# Quad_FC_power_V10_0.net
KiCad netlist of a schematic drawn in Altium Designer
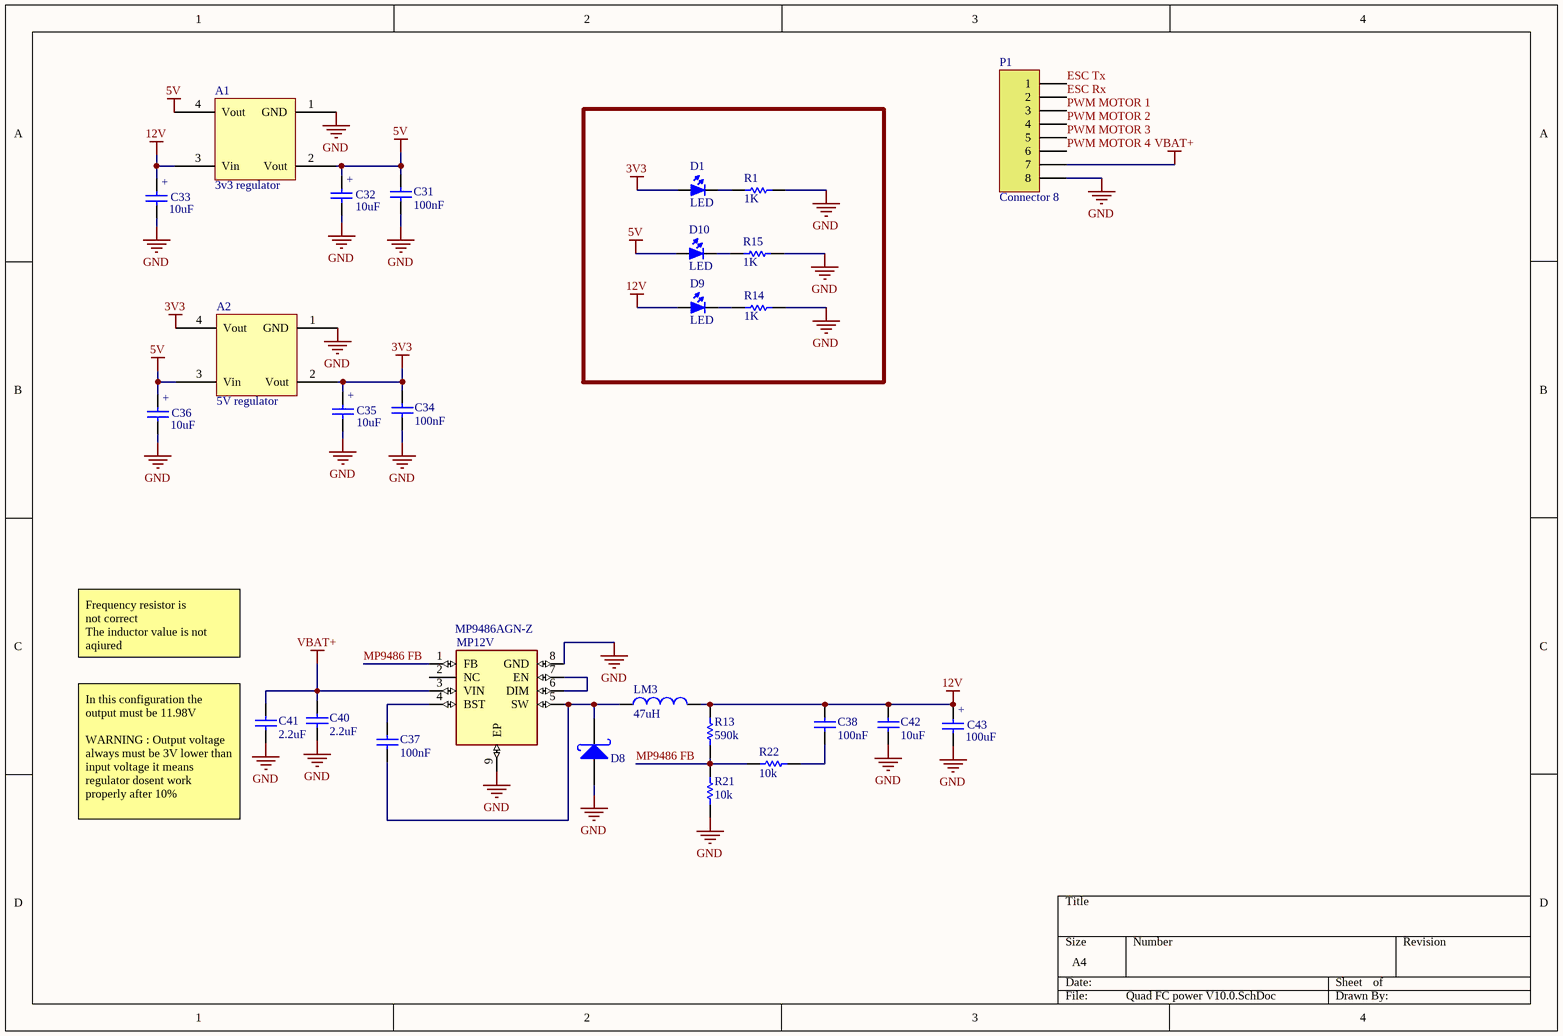
[diagram p0: Quad FC power V10.0.SchDoc]

(export (version "E")
  (design (tool "Eeschema 10.0.6"))
  (components
    (comp (ref "A1")
      (value "3v3 regulator")
      (footprint "SOT230P700X180-4N")
      (libsource (lib "Integrated_Library1") (part "ams1117"))
    )
    (comp (ref "A2")
      (value "5V regulator")
      (footprint "SOT230P700X180-4N")
      (libsource (lib "Integrated_Library1") (part "ams1117"))
    )
    (comp (ref "C31")
      (value "100nF")
      (footprint "CAP0603")
      (description "F407VET6 Power CAP")
      (fields (field (name "DESIGNER") "Abbas Basereh"))
      (libsource (lib "2017AbbasBasereh9365731239 -ver1") (part "CAP SMD PACKAGE"))
    )
    (comp (ref "C32")
      (value "10uF")
      (footprint "MY_CAP_SMD-B")
      (description "3.5X2.8MM")
      (libsource (lib "AMINLIB") (part "CAP_TANTAL_B"))
    )
    (comp (ref "C33")
      (value "10uF")
      (footprint "MY_CAP_SMD-B")
      (description "3.5X2.8MM")
      (libsource (lib "AMINLIB") (part "CAP_TANTAL_B"))
    )
    (comp (ref "C34")
      (value "100nF")
      (footprint "CAP0603")
      (description "F407VET6 Power CAP")
      (fields (field (name "DESIGNER") "Abbas Basereh"))
      (libsource (lib "2017AbbasBasereh9365731239 -ver1") (part "CAP SMD PACKAGE"))
    )
    (comp (ref "C35")
      (value "10uF")
      (footprint "MY_CAP_SMD-B")
      (description "3.5X2.8MM")
      (libsource (lib "AMINLIB") (part "CAP_TANTAL_B"))
    )
    (comp (ref "C36")
      (value "10uF")
      (footprint "MY_CAP_SMD-B")
      (description "3.5X2.8MM")
      (libsource (lib "AMINLIB") (part "CAP_TANTAL_B"))
    )
    (comp (ref "C37")
      (value "100nF")
      (footprint "CAP0603")
      (description "F407VET6 Power CAP")
      (fields (field (name "DESIGNER") "Abbas Basereh"))
      (libsource (lib "2017AbbasBasereh9365731239 -ver1") (part "CAP SMD PACKAGE"))
    )
    (comp (ref "C38")
      (value "100nF")
      (footprint "CAP0603")
      (description "F407VET6 Power CAP")
      (fields (field (name "DESIGNER") "Abbas Basereh"))
      (libsource (lib "2017AbbasBasereh9365731239 -ver1") (part "CAP SMD PACKAGE"))
    )
    (comp (ref "C40")
      (value "2.2uF")
      (footprint "CAPC3413X12N")
      (description "CAP 0805")
      (fields (field (name "DESIGNER") "Abbas Basereh"))
      (libsource (lib "2017AbbasBasereh9365731239 -ver1") (part "CAP SMD 0805"))
    )
    (comp (ref "C41")
      (value "2.2uF")
      (footprint "CAPC3413X12N")
      (description "CAP 0805")
      (fields (field (name "DESIGNER") "Abbas Basereh"))
      (libsource (lib "2017AbbasBasereh9365731239 -ver1") (part "CAP SMD 0805"))
    )
    (comp (ref "C42")
      (value "10uF")
      (footprint "CAPC3413X12N")
      (description "CAP 0805")
      (fields (field (name "DESIGNER") "Abbas Basereh"))
      (libsource (lib "2017AbbasBasereh9365731239 -ver1") (part "CAP SMD 0805"))
    )
    (comp (ref "C43")
      (value "100uF")
      (footprint "MY_CAP_SMD-B")
      (description "3.5X2.8MM")
      (libsource (lib "AMINLIB") (part "CAP_TANTAL_B"))
    )
    (comp (ref "D1")
      (value "LED")
      (footprint "0603 - LED")
      (description "Led")
      (fields (field (name "PUBLISHER") "Altium Limited"))
      (libsource (lib "Sajad_Altium_Library") (part "LED"))
    )
    (comp (ref "D8")
      (value "SS34")
      (footprint "SS34:DIOM4226X244N")
      (fields
        (field (name "MANUFACTURER") "ON Semiconductor/Fairchild")
        (field (name "DESIGNER") "Abbas Basereh")
      )
      (libsource (lib "2017AbbasBasereh9365731239 -ver1") (part "1n5822 SMD"))
    )
    (comp (ref "D9")
      (value "LED")
      (footprint "0603 - LED")
      (description "Led")
      (fields (field (name "PUBLISHER") "Altium Limited"))
      (libsource (lib "Sajad_Altium_Library") (part "LED"))
    )
    (comp (ref "D10")
      (value "LED")
      (footprint "0603 - LED")
      (description "Led")
      (fields (field (name "PUBLISHER") "Altium Limited"))
      (libsource (lib "Sajad_Altium_Library") (part "LED"))
    )
    (comp (ref "LM3")
      (value "47uH")
      (footprint "RLS-105:IND_RLS-105")
      (description "Inductor")
      (fields (field (name "PUBLISHER") "Altium Limited"))
      (libsource (lib "2017AbbasBasereh9365731239 -ver1") (part "L SMA 0.25W"))
    )
    (comp (ref "MP12V")
      (value "MP9486AGN-Z")
      (footprint "SOIC127P600X170-9N")
      (description "Buck Switching Regulator IC Positive Fixed 5V 1 Output 1A 8-SOIC (0.154, 3.90mm Width) Exposed Pad")
      (fields (field (name "MF") "Monolithic Power"))
      (libsource (lib "MP9486AGN-Z") (part "MP9486AGN-Z"))
    )
    (comp (ref "P1")
      (value "Connector 8")
      (footprint "JST B8B-PH-K")
      (description "Connector, 8-Pin2.5mm")
      (fields (field (name "PUBLISHER") "Altium Limited"))
      (libsource (lib "Sajad_Altium_Library") (part "Connector1x8"))
    )
    (comp (ref "R1")
      (value "1K")
      (footprint "RES0603")
      (description "TOTAL SMD RESISTOR PACK")
      (fields (field (name "DESIGNER") "Abbas Basereh"))
      (libsource (lib "2017AbbasBasereh9365731239 -ver1") (part "RES SMD PACKAGE"))
    )
    (comp (ref "R13")
      (value "590k")
      (footprint "RES0603")
      (description "To Limit current")
      (fields (field (name "DESIGNER") "Abbas Basereh"))
      (libsource (lib "2017AbbasBasereh9365731239 -ver1") (part "RES SMD PACKAGE"))
    )
    (comp (ref "R14")
      (value "1K")
      (footprint "RES0603")
      (description "TOTAL SMD RESISTOR PACK")
      (fields (field (name "DESIGNER") "Abbas Basereh"))
      (libsource (lib "2017AbbasBasereh9365731239 -ver1") (part "RES SMD PACKAGE"))
    )
    (comp (ref "R15")
      (value "1K")
      (footprint "RES0603")
      (description "TOTAL SMD RESISTOR PACK")
      (fields (field (name "DESIGNER") "Abbas Basereh"))
      (libsource (lib "2017AbbasBasereh9365731239 -ver1") (part "RES SMD PACKAGE"))
    )
    (comp (ref "R21")
      (value "10k")
      (footprint "RES0603")
      (description "To Limit current")
      (fields (field (name "DESIGNER") "Abbas Basereh"))
      (libsource (lib "2017AbbasBasereh9365731239 -ver1") (part "RES SMD PACKAGE"))
    )
    (comp (ref "R22")
      (value "10k")
      (footprint "RES0603")
      (description "To Limit current")
      (fields (field (name "DESIGNER") "Abbas Basereh"))
      (libsource (lib "2017AbbasBasereh9365731239 -ver1") (part "RES SMD PACKAGE"))
    )
  )
  (nets
    (net (code "1") (name "/ESC Rx") (class "Default")
      (node (ref "P1") (pin "2") (pinfunction "2_2") (pintype "passive"))
    )
    (net (code "2") (name "/ESC Tx") (class "Default")
      (node (ref "P1") (pin "1") (pinfunction "1_1") (pintype "passive"))
    )
    (net (code "3") (name "/MP9486 FB") (class "Default")
      (node (ref "MP12V") (pin "1") (pinfunction "FB_1") (pintype "bidirectional"))
      (node (ref "R13") (pin "1") (pinfunction "1_1") (pintype "passive"))
      (node (ref "R21") (pin "2") (pinfunction "2_2") (pintype "passive"))
      (node (ref "R22") (pin "2") (pinfunction "2_2") (pintype "passive"))
    )
    (net (code "4") (name "/PWM MOTOR 1") (class "Default")
      (node (ref "P1") (pin "3") (pinfunction "3_3") (pintype "passive"))
    )
    (net (code "5") (name "/PWM MOTOR 2") (class "Default")
      (node (ref "P1") (pin "4") (pinfunction "4_4") (pintype "passive"))
    )
    (net (code "6") (name "/PWM MOTOR 3") (class "Default")
      (node (ref "P1") (pin "5") (pinfunction "5_5") (pintype "passive"))
    )
    (net (code "7") (name "/PWM MOTOR 4") (class "Default")
      (node (ref "P1") (pin "6") (pinfunction "6_6") (pintype "passive"))
    )
    (net (code "8") (name "3V3") (class "Default")
      (node (ref "A2") (pin "2") (pinfunction "Vout_2") (pintype "passive"))
      (node (ref "A2") (pin "4") (pinfunction "Vout_4") (pintype "passive"))
      (node (ref "C34") (pin "2") (pinfunction "2_2") (pintype "passive"))
      (node (ref "C35") (pin "+") (pinfunction "+_+") (pintype "passive"))
      (node (ref "D1") (pin "1") (pinfunction "A_1") (pintype "passive"))
    )
    (net (code "9") (name "5V") (class "Default")
      (node (ref "A1") (pin "2") (pinfunction "Vout_2") (pintype "passive"))
      (node (ref "A1") (pin "4") (pinfunction "Vout_4") (pintype "passive"))
      (node (ref "A2") (pin "3") (pinfunction "Vin_3") (pintype "passive"))
      (node (ref "C31") (pin "2") (pinfunction "2_2") (pintype "passive"))
      (node (ref "C32") (pin "+") (pinfunction "+_+") (pintype "passive"))
      (node (ref "C36") (pin "+") (pinfunction "+_+") (pintype "passive"))
      (node (ref "D10") (pin "1") (pinfunction "A_1") (pintype "passive"))
    )
    (net (code "10") (name "12V") (class "Default")
      (node (ref "A1") (pin "3") (pinfunction "Vin_3") (pintype "passive"))
      (node (ref "C33") (pin "+") (pinfunction "+_+") (pintype "passive"))
      (node (ref "C38") (pin "2") (pinfunction "2_2") (pintype "passive"))
      (node (ref "C42") (pin "2") (pinfunction "2_2") (pintype "passive"))
      (node (ref "C43") (pin "+") (pinfunction "+_+") (pintype "passive"))
      (node (ref "D9") (pin "1") (pinfunction "A_1") (pintype "passive"))
      (node (ref "LM3") (pin "2") (pinfunction "2_2") (pintype "passive"))
      (node (ref "R13") (pin "2") (pinfunction "2_2") (pintype "passive"))
    )
    (net (code "11") (name "GND") (class "Default")
      (node (ref "A1") (pin "1") (pinfunction "GND_1") (pintype "passive"))
      (node (ref "A2") (pin "1") (pinfunction "GND_1") (pintype "passive"))
      (node (ref "C31") (pin "1") (pinfunction "1_1") (pintype "passive"))
      (node (ref "C32") (pin "-") (pinfunction "-_-") (pintype "passive"))
      (node (ref "C33") (pin "-") (pinfunction "-_-") (pintype "passive"))
      (node (ref "C34") (pin "1") (pinfunction "1_1") (pintype "passive"))
      (node (ref "C35") (pin "-") (pinfunction "-_-") (pintype "passive"))
      (node (ref "C36") (pin "-") (pinfunction "-_-") (pintype "passive"))
      (node (ref "C40") (pin "2") (pinfunction "2_2") (pintype "passive"))
      (node (ref "C41") (pin "2") (pinfunction "2_2") (pintype "passive"))
      (node (ref "C42") (pin "1") (pinfunction "1_1") (pintype "passive"))
      (node (ref "C43") (pin "-") (pinfunction "-_-") (pintype "passive"))
      (node (ref "D8") (pin "1") (pinfunction "A_1") (pintype "passive"))
      (node (ref "MP12V") (pin "8") (pinfunction "GND_8") (pintype "bidirectional"))
      (node (ref "MP12V") (pin "9") (pinfunction "EP_9") (pintype "bidirectional"))
      (node (ref "P1") (pin "8") (pinfunction "8_8") (pintype "passive"))
      (node (ref "R1") (pin "2") (pinfunction "2_2") (pintype "passive"))
      (node (ref "R14") (pin "2") (pinfunction "2_2") (pintype "passive"))
      (node (ref "R15") (pin "2") (pinfunction "2_2") (pintype "passive"))
      (node (ref "R21") (pin "1") (pinfunction "1_1") (pintype "passive"))
    )
    (net (code "12") (name "Net-(C38-Pad1)") (class "Default")
      (node (ref "C38") (pin "1") (pinfunction "1_1") (pintype "passive"))
      (node (ref "R22") (pin "1") (pinfunction "1_1") (pintype "passive"))
    )
    (net (code "13") (name "Net-(D1-K)") (class "Default")
      (node (ref "D1") (pin "2") (pinfunction "K_2") (pintype "passive"))
      (node (ref "R1") (pin "1") (pinfunction "1_1") (pintype "passive"))
    )
    (net (code "14") (name "Net-(D8-K)") (class "Default")
      (node (ref "C37") (pin "1") (pinfunction "1_1") (pintype "passive"))
      (node (ref "D8") (pin "2") (pinfunction "K_2") (pintype "passive"))
      (node (ref "LM3") (pin "1") (pinfunction "1_1") (pintype "passive"))
      (node (ref "MP12V") (pin "5") (pinfunction "SW_5") (pintype "bidirectional"))
    )
    (net (code "15") (name "Net-(D9-K)") (class "Default")
      (node (ref "D9") (pin "2") (pinfunction "K_2") (pintype "passive"))
      (node (ref "R14") (pin "1") (pinfunction "1_1") (pintype "passive"))
    )
    (net (code "16") (name "Net-(D10-K)") (class "Default")
      (node (ref "D10") (pin "2") (pinfunction "K_2") (pintype "passive"))
      (node (ref "R15") (pin "1") (pinfunction "1_1") (pintype "passive"))
    )
    (net (code "17") (name "Net-(MP12V-BST)") (class "Default")
      (node (ref "C37") (pin "2") (pinfunction "2_2") (pintype "passive"))
      (node (ref "MP12V") (pin "4") (pinfunction "BST_4") (pintype "bidirectional"))
    )
    (net (code "18") (name "Net-(MP12V-DIM)") (class "Default")
      (node (ref "MP12V") (pin "6") (pinfunction "DIM_6") (pintype "bidirectional"))
      (node (ref "MP12V") (pin "7") (pinfunction "EN_7") (pintype "bidirectional"))
    )
    (net (code "19") (name "VBAT+") (class "Default")
      (node (ref "C40") (pin "1") (pinfunction "1_1") (pintype "passive"))
      (node (ref "C41") (pin "1") (pinfunction "1_1") (pintype "passive"))
      (node (ref "MP12V") (pin "3") (pinfunction "VIN_3") (pintype "bidirectional"))
      (node (ref "P1") (pin "7") (pinfunction "7_7") (pintype "passive"))
    )
    (net (code "20") (name "unconnected-(MP12V-NC-Pad2)") (class "Default")
      (node (ref "MP12V") (pin "2") (pinfunction "NC_2") (pintype "passive"))
    )
  )
)
